# hw.net
KiCad netlist of a schematic drawn in EAGLE
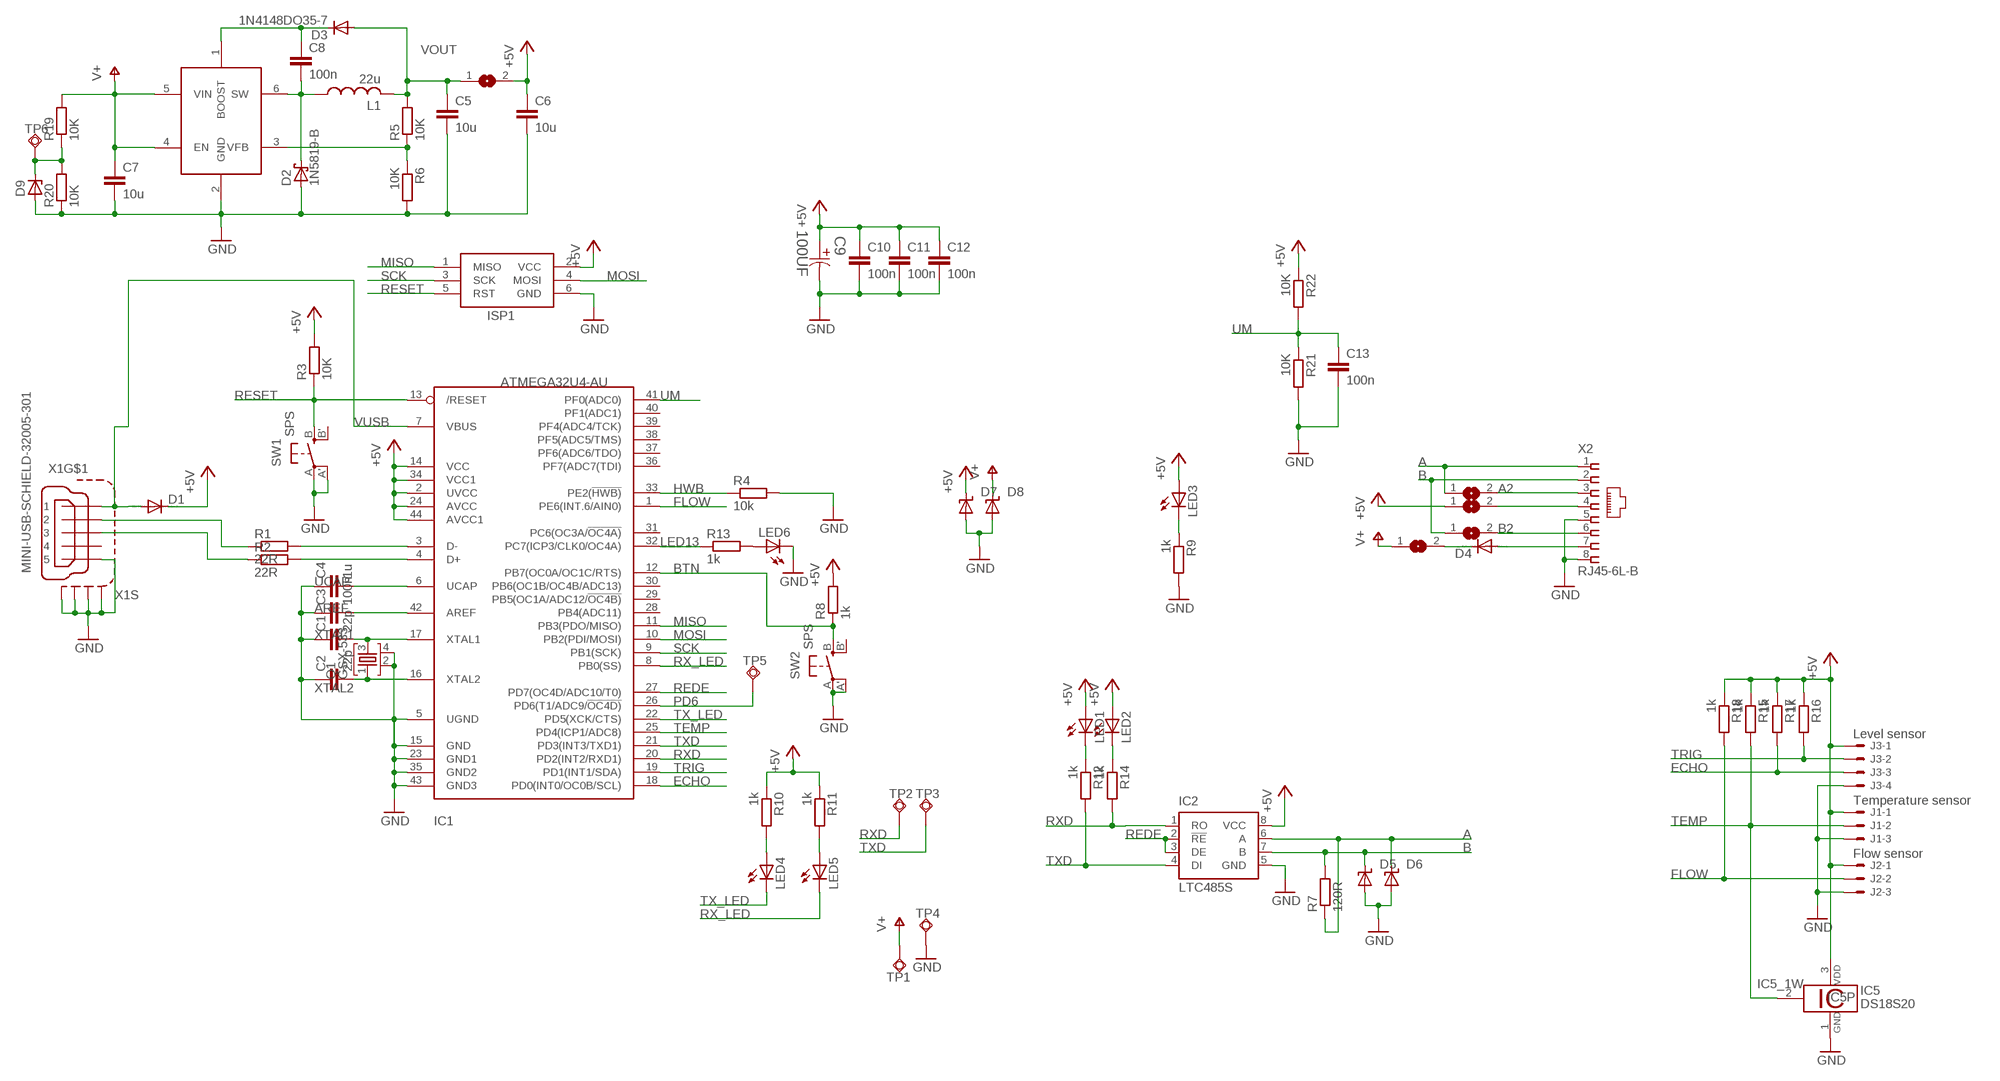
[diagram p0: schematic, sheet 1]

(export (version "E")
  (design (tool "Eeschema 10.0.6"))
  (components
    (comp (ref "C1")
      (value "22p")
      (footprint "eagle-import:C0805K")
      (libsource (lib "eagle-import") (part "C-EUC0805K"))
    )
    (comp (ref "C2")
      (value "22p")
      (footprint "eagle-import:C0805K")
      (libsource (lib "eagle-import") (part "C-EUC0805K"))
    )
    (comp (ref "C3")
      (value "100n")
      (footprint "eagle-import:C0805K")
      (libsource (lib "eagle-import") (part "C-EUC0805K"))
    )
    (comp (ref "C4")
      (value "1u")
      (footprint "eagle-import:C0805K")
      (libsource (lib "eagle-import") (part "C-EUC0805K"))
    )
    (comp (ref "C5")
      (value "10u")
      (footprint "eagle-import:C0805K")
      (libsource (lib "eagle-import") (part "C-EUC0805K"))
    )
    (comp (ref "C6")
      (value "10u")
      (footprint "eagle-import:C0805K")
      (libsource (lib "eagle-import") (part "C-EUC0805K"))
    )
    (comp (ref "C7")
      (value "10u")
      (footprint "eagle-import:C0805K")
      (libsource (lib "eagle-import") (part "C-EUC0805K"))
    )
    (comp (ref "C8")
      (value "100n")
      (footprint "eagle-import:C0805K")
      (libsource (lib "eagle-import") (part "C-EUC0805K"))
    )
    (comp (ref "C9")
      (value "100UF")
      (footprint "eagle-import:CAPAE660X610N")
      (fields (field (name "MPN") "EEE-FK0J101AP") (field (name "TOLERANCE") "±20 %"))
      (libsource (lib "eagle-import") (part "EEE--CASE-DFK0J101AP"))
    )
    (comp (ref "C10")
      (value "100n")
      (footprint "eagle-import:C0805K")
      (libsource (lib "eagle-import") (part "C-EUC0805K"))
    )
    (comp (ref "C11")
      (value "100n")
      (footprint "eagle-import:C0805K")
      (libsource (lib "eagle-import") (part "C-EUC0805K"))
    )
    (comp (ref "C12")
      (value "100n")
      (footprint "eagle-import:C0805K")
      (libsource (lib "eagle-import") (part "C-EUC0805K"))
    )
    (comp (ref "C13")
      (value "100n")
      (footprint "eagle-import:C0805K")
      (libsource (lib "eagle-import") (part "C-EUC0805K"))
    )
    (comp (ref "D1")
      (value "DIODE-MICROMELF-W")
      (footprint "eagle-import:MICROMELF-W")
      (libsource (lib "eagle-import") (part "DIODE-MICROMELF-W"))
    )
    (comp (ref "D2")
      (value "1N5819-B")
      (footprint "eagle-import:DO41-7.6")
      (libsource (lib "eagle-import") (part "1N5819-B"))
    )
    (comp (ref "D3")
      (value "1N4148DO35-7")
      (footprint "eagle-import:DO35-7")
      (libsource (lib "eagle-import") (part "1N4148DO35-7"))
    )
    (comp (ref "D4")
      (value "DIODE-MINIMELF")
      (footprint "eagle-import:MINIMELF")
      (libsource (lib "eagle-import") (part "diode_210_DIODE-MINIMELF"))
    )
    (comp (ref "D5")
      (value "SUPPRESSOR-SMBG")
      (footprint "eagle-import:SMBG")
      (libsource (lib "eagle-import") (part "SUPPRESSOR-SMBG"))
    )
    (comp (ref "D6")
      (value "SUPPRESSOR-SMBG")
      (footprint "eagle-import:SMBG")
      (libsource (lib "eagle-import") (part "SUPPRESSOR-SMBG"))
    )
    (comp (ref "D7")
      (value "SUPPRESSOR-SMBG")
      (footprint "eagle-import:SMBG")
      (libsource (lib "eagle-import") (part "SUPPRESSOR-SMBG"))
    )
    (comp (ref "D8")
      (value "SUPPRESSOR-SMBG")
      (footprint "eagle-import:SMBG")
      (libsource (lib "eagle-import") (part "SUPPRESSOR-SMBG"))
    )
    (comp (ref "D9")
      (value "ZENER-DIODESMB")
      (footprint "eagle-import:SMB")
      (libsource (lib "eagle-import") (part "ZENER-DIODESMB"))
    )
    (comp (ref "IC1")
      (value "ATMEGA32U4-AU")
      (footprint "eagle-import:TQFP44")
      (libsource (lib "eagle-import") (part "ATMEGA32U4-AU"))
    )
    (comp (ref "IC2")
      (value "LTC485S")
      (footprint "eagle-import:SOIC8")
      (libsource (lib "eagle-import") (part "LTC485S"))
    )
    (comp (ref "IC3")
      (value "MCP16301/H")
      (footprint "eagle-import:SOT23-6")
      (libsource (lib "eagle-import") (part "MCP16301/H"))
    )
    (comp (ref "IC5")
      (value "DS18S20")
      (footprint "eagle-import:TO92-")
      (fields (field (name "SPICEPREFIX") "X"))
      (libsource (lib "eagle-import") (part "DS18S20"))
    )
    (comp (ref "ISP1")
      (value "AVRISP-6")
      (footprint "eagle-import:AVRISP")
      (libsource (lib "eagle-import") (part "AVRISP-6"))
    )
    (comp (ref "J1")
      (value "Temperature sensor")
      (footprint "eagle-import:6410-03")
      (fields (field (name "MF") "MOLEX"))
      (libsource (lib "eagle-import") (part "22-?-0327-2031"))
    )
    (comp (ref "J2")
      (value "Flow sensor")
      (footprint "eagle-import:6410-03")
      (fields (field (name "MF") "MOLEX"))
      (libsource (lib "eagle-import") (part "22-?-0327-2031"))
    )
    (comp (ref "J3")
      (value "Level sensor")
      (footprint "eagle-import:6410-04")
      (fields (field (name "MF") "MOLEX"))
      (libsource (lib "eagle-import") (part "22-?-0427-2041"))
    )
    (comp (ref "L1")
      (value "22u")
      (footprint "eagle-import:0207_12")
      (libsource (lib "eagle-import") (part "L-US0207/12"))
    )
    (comp (ref "LED1")
      (value "LEDCHIPLED_0805")
      (footprint "eagle-import:CHIPLED_0805")
      (libsource (lib "eagle-import") (part "LEDCHIPLED_0805"))
    )
    (comp (ref "LED2")
      (value "LEDCHIPLED_0805")
      (footprint "eagle-import:CHIPLED_0805")
      (libsource (lib "eagle-import") (part "LEDCHIPLED_0805"))
    )
    (comp (ref "LED3")
      (value "LEDCHIPLED_0805")
      (footprint "eagle-import:CHIPLED_0805")
      (libsource (lib "eagle-import") (part "LEDCHIPLED_0805"))
    )
    (comp (ref "LED4")
      (value "LEDCHIPLED_0805")
      (footprint "eagle-import:CHIPLED_0805")
      (libsource (lib "eagle-import") (part "LEDCHIPLED_0805"))
    )
    (comp (ref "LED5")
      (value "LEDCHIPLED_0805")
      (footprint "eagle-import:CHIPLED_0805")
      (libsource (lib "eagle-import") (part "LEDCHIPLED_0805"))
    )
    (comp (ref "LED6")
      (value "LEDCHIPLED_0805")
      (footprint "eagle-import:CHIPLED_0805")
      (libsource (lib "eagle-import") (part "LEDCHIPLED_0805"))
    )
    (comp (ref "Q1")
      (value "GSX-533")
      (footprint "eagle-import:5032")
      (libsource (lib "eagle-import") (part "GSX-533"))
    )
    (comp (ref "R1")
      (value "22R")
      (footprint "eagle-import:M0805")
      (libsource (lib "eagle-import") (part "R-EU_M0805"))
    )
    (comp (ref "R2")
      (value "22R")
      (footprint "eagle-import:M0805")
      (libsource (lib "eagle-import") (part "R-EU_M0805"))
    )
    (comp (ref "R3")
      (value "10K")
      (footprint "eagle-import:M0805")
      (libsource (lib "eagle-import") (part "R-EU_M0805"))
    )
    (comp (ref "R4")
      (value "10k")
      (footprint "eagle-import:M0805")
      (libsource (lib "eagle-import") (part "R-EU_M0805"))
    )
    (comp (ref "R5")
      (value "10K")
      (footprint "eagle-import:M0805")
      (libsource (lib "eagle-import") (part "R-EU_M0805"))
    )
    (comp (ref "R6")
      (value "10K")
      (footprint "eagle-import:M0805")
      (libsource (lib "eagle-import") (part "R-EU_M0805"))
    )
    (comp (ref "R7")
      (value "120R")
      (footprint "eagle-import:M0805")
      (libsource (lib "eagle-import") (part "R-EU_M0805"))
    )
    (comp (ref "R8")
      (value "1k")
      (footprint "eagle-import:M0805")
      (libsource (lib "eagle-import") (part "R-EU_M0805"))
    )
    (comp (ref "R9")
      (value "1k")
      (footprint "eagle-import:M0805")
      (libsource (lib "eagle-import") (part "R-EU_M0805"))
    )
    (comp (ref "R10")
      (value "1k")
      (footprint "eagle-import:M0805")
      (libsource (lib "eagle-import") (part "R-EU_M0805"))
    )
    (comp (ref "R11")
      (value "1k")
      (footprint "eagle-import:M0805")
      (libsource (lib "eagle-import") (part "R-EU_M0805"))
    )
    (comp (ref "R12")
      (value "1k")
      (footprint "eagle-import:M0805")
      (libsource (lib "eagle-import") (part "R-EU_M0805"))
    )
    (comp (ref "R13")
      (value "1k")
      (footprint "eagle-import:M0805")
      (libsource (lib "eagle-import") (part "R-EU_M0805"))
    )
    (comp (ref "R14")
      (value "1k")
      (footprint "eagle-import:M0805")
      (libsource (lib "eagle-import") (part "R-EU_M0805"))
    )
    (comp (ref "R15")
      (value "1k")
      (footprint "eagle-import:M0805")
      (libsource (lib "eagle-import") (part "R-EU_M0805"))
    )
    (comp (ref "R16")
      (value "1k")
      (footprint "eagle-import:M0805")
      (libsource (lib "eagle-import") (part "R-EU_M0805"))
    )
    (comp (ref "R17")
      (value "1k")
      (footprint "eagle-import:M0805")
      (libsource (lib "eagle-import") (part "R-EU_M0805"))
    )
    (comp (ref "R18")
      (value "1k")
      (footprint "eagle-import:M0805")
      (libsource (lib "eagle-import") (part "R-EU_M0805"))
    )
    (comp (ref "R19")
      (value "10K")
      (footprint "eagle-import:M0805")
      (libsource (lib "eagle-import") (part "R-EU_M0805"))
    )
    (comp (ref "R20")
      (value "10K")
      (footprint "eagle-import:M0805")
      (libsource (lib "eagle-import") (part "R-EU_M0805"))
    )
    (comp (ref "R21")
      (value "10K")
      (footprint "eagle-import:M0805")
      (libsource (lib "eagle-import") (part "R-EU_M0805"))
    )
    (comp (ref "R22")
      (value "10K")
      (footprint "eagle-import:M0805")
      (libsource (lib "eagle-import") (part "R-EU_M0805"))
    )
    (comp (ref "SJ1") (value "SJ") (footprint "eagle-import:SJ") (libsource (lib "eagle-import") (part "SJ")))
    (comp (ref "SJ2") (value "SJ") (footprint "eagle-import:SJ") (libsource (lib "eagle-import") (part "SJ")))
    (comp (ref "SJ3") (value "SJ") (footprint "eagle-import:SJ") (libsource (lib "eagle-import") (part "SJ")))
    (comp (ref "SJ4") (value "SJ") (footprint "eagle-import:SJ") (libsource (lib "eagle-import") (part "SJ")))
    (comp (ref "SJ5") (value "SJ") (footprint "eagle-import:SJ") (libsource (lib "eagle-import") (part "SJ")))
    (comp (ref "SW1")
      (value "SPS")
      (footprint "eagle-import:EVQ-Q2")
      (libsource (lib "eagle-import") (part "SPST_TACT-EVQQ2"))
    )
    (comp (ref "SW2")
      (value "SPS")
      (footprint "eagle-import:EVQ-Q2")
      (libsource (lib "eagle-import") (part "SPST_TACT-EVQQ2"))
    )
    (comp (ref "TP1")
      (value "TPSQTP20SQ")
      (footprint "eagle-import:TP20SQ")
      (libsource (lib "eagle-import") (part "TPSQTP20SQ"))
    )
    (comp (ref "TP2")
      (value "TPSQTP20SQ")
      (footprint "eagle-import:TP20SQ")
      (libsource (lib "eagle-import") (part "TPSQTP20SQ"))
    )
    (comp (ref "TP3")
      (value "TPSQTP20SQ")
      (footprint "eagle-import:TP20SQ")
      (libsource (lib "eagle-import") (part "TPSQTP20SQ"))
    )
    (comp (ref "TP4")
      (value "TPSQTP20SQ")
      (footprint "eagle-import:TP20SQ")
      (libsource (lib "eagle-import") (part "TPSQTP20SQ"))
    )
    (comp (ref "TP5")
      (value "TPSQTP20SQ")
      (footprint "eagle-import:TP20SQ")
      (libsource (lib "eagle-import") (part "TPSQTP20SQ"))
    )
    (comp (ref "TP6")
      (value "TPSQTP20SQ")
      (footprint "eagle-import:TP20SQ")
      (libsource (lib "eagle-import") (part "TPSQTP20SQ"))
    )
    (comp (ref "X1")
      (value "MINI-USB-SCHIELD-32005-301")
      (footprint "eagle-import:32005-301")
      (libsource (lib "eagle-import") (part "MINI-USB-SCHIELD-32005-301"))
    )
    (comp (ref "X2")
      (value "RJ45-6L-B")
      (footprint "eagle-import:RJ45-NO-SHIELD")
      (libsource (lib "eagle-import") (part "RJ45-6L-B"))
    )
  )
  (nets
    (net (code "1") (name "+5V") (class "Default")
      (node (ref "C10") (pin "1") (pinfunction "1_1") (pintype "passive"))
      (node (ref "C11") (pin "1") (pinfunction "1_1") (pintype "passive"))
      (node (ref "C12") (pin "1") (pinfunction "1_1") (pintype "passive"))
      (node (ref "C6") (pin "1") (pinfunction "1_1") (pintype "passive"))
      (node (ref "C9") (pin "1") (pinfunction "1_1") (pintype "passive"))
      (node (ref "D1") (pin "C") (pinfunction "C_C") (pintype "passive"))
      (node (ref "D7") (pin "C") (pinfunction "C_C") (pintype "passive"))
      (node (ref "IC1") (pin "14") (pinfunction "VCC_14") (pintype "bidirectional"))
      (node (ref "IC1") (pin "2") (pinfunction "UVCC_2") (pintype "bidirectional"))
      (node (ref "IC1") (pin "24") (pinfunction "AVCC_24") (pintype "bidirectional"))
      (node (ref "IC1") (pin "34") (pinfunction "VCC1_34") (pintype "bidirectional"))
      (node (ref "IC1") (pin "44") (pinfunction "AVCC1_44") (pintype "bidirectional"))
      (node (ref "IC2") (pin "8") (pinfunction "VCC_8") (pintype "input"))
      (node (ref "IC5") (pin "3") (pinfunction "VDD_3") (pintype "power_in"))
      (node (ref "ISP1") (pin "2") (pinfunction "VCC_2") (pintype "power_in"))
      (node (ref "J1") (pin "1") (pinfunction "S_1") (pintype "passive"))
      (node (ref "J2") (pin "1") (pinfunction "S_1") (pintype "passive"))
      (node (ref "J3") (pin "1") (pinfunction "S_1") (pintype "passive"))
      (node (ref "LED1") (pin "A") (pinfunction "A_A") (pintype "passive"))
      (node (ref "LED2") (pin "A") (pinfunction "A_A") (pintype "passive"))
      (node (ref "LED3") (pin "A") (pinfunction "A_A") (pintype "passive"))
      (node (ref "R10") (pin "1") (pinfunction "1_1") (pintype "passive"))
      (node (ref "R11") (pin "1") (pinfunction "1_1") (pintype "passive"))
      (node (ref "R15") (pin "1") (pinfunction "1_1") (pintype "passive"))
      (node (ref "R16") (pin "1") (pinfunction "1_1") (pintype "passive"))
      (node (ref "R17") (pin "1") (pinfunction "1_1") (pintype "passive"))
      (node (ref "R18") (pin "1") (pinfunction "1_1") (pintype "passive"))
      (node (ref "R22") (pin "1") (pinfunction "1_1") (pintype "passive"))
      (node (ref "R3") (pin "2") (pinfunction "2_2") (pintype "passive"))
      (node (ref "R8") (pin "2") (pinfunction "2_2") (pintype "passive"))
      (node (ref "SJ4") (pin "1") (pinfunction "1_1") (pintype "passive"))
      (node (ref "SJ5") (pin "2") (pinfunction "2_2") (pintype "passive"))
    )
    (net (code "2") (name "/A") (class "Default")
      (node (ref "D6") (pin "C") (pinfunction "C_C") (pintype "passive"))
      (node (ref "IC2") (pin "6") (pinfunction "A_6") (pintype "bidirectional"))
      (node (ref "R7") (pin "1") (pinfunction "1_1") (pintype "passive"))
      (node (ref "SJ1") (pin "1") (pinfunction "1_1") (pintype "passive"))
      (node (ref "X2") (pin "1") (pinfunction "1_1") (pintype "passive"))
    )
    (net (code "3") (name "/A2") (class "Default")
      (node (ref "SJ1") (pin "2") (pinfunction "2_2") (pintype "passive"))
      (node (ref "X2") (pin "3") (pinfunction "3_3") (pintype "passive"))
    )
    (net (code "4") (name "/AREF") (class "Default")
      (node (ref "C3") (pin "2") (pinfunction "2_2") (pintype "passive"))
      (node (ref "IC1") (pin "42") (pinfunction "AREF_42") (pintype "bidirectional"))
    )
    (net (code "5") (name "/B") (class "Default")
      (node (ref "D5") (pin "C") (pinfunction "C_C") (pintype "passive"))
      (node (ref "IC2") (pin "7") (pinfunction "B_7") (pintype "bidirectional"))
      (node (ref "R7") (pin "2") (pinfunction "2_2") (pintype "passive"))
      (node (ref "SJ2") (pin "1") (pinfunction "1_1") (pintype "passive"))
      (node (ref "X2") (pin "2") (pinfunction "2_2") (pintype "passive"))
    )
    (net (code "6") (name "/B2") (class "Default")
      (node (ref "SJ2") (pin "2") (pinfunction "2_2") (pintype "passive"))
      (node (ref "X2") (pin "6") (pinfunction "6_6") (pintype "passive"))
    )
    (net (code "7") (name "/BTN") (class "Default")
      (node (ref "IC1") (pin "12") (pinfunction "PB7(OC0A/OC1C/RTS)_12") (pintype "bidirectional"))
      (node (ref "R8") (pin "1") (pinfunction "1_1") (pintype "passive"))
      (node (ref "SW2") (pin "B") (pinfunction "S_B") (pintype "passive"))
    )
    (net (code "8") (name "/ECHO") (class "Default")
      (node (ref "IC1") (pin "18") (pinfunction "PD0(INT0/OC0B/SCL)_18") (pintype "bidirectional"))
      (node (ref "J3") (pin "3") (pinfunction "S_3") (pintype "passive"))
      (node (ref "R17") (pin "2") (pinfunction "2_2") (pintype "passive"))
    )
    (net (code "9") (name "/FLOW") (class "Default")
      (node (ref "IC1") (pin "1") (pinfunction "PE6(INT.6/AIN0)_1") (pintype "bidirectional"))
      (node (ref "J2") (pin "2") (pinfunction "S_2") (pintype "passive"))
      (node (ref "R18") (pin "2") (pinfunction "2_2") (pintype "passive"))
    )
    (net (code "10") (name "/HWB") (class "Default")
      (node (ref "IC1") (pin "33") (pinfunction "PE2(~{HWB})_33") (pintype "bidirectional"))
      (node (ref "R4") (pin "1") (pinfunction "1_1") (pintype "passive"))
    )
    (net (code "11") (name "/LED13") (class "Default")
      (node (ref "IC1") (pin "32") (pinfunction "PC7(ICP3/CLK0/OC4A)_32") (pintype "bidirectional"))
      (node (ref "R13") (pin "1") (pinfunction "1_1") (pintype "passive"))
    )
    (net (code "12") (name "/MISO") (class "Default")
      (node (ref "IC1") (pin "11") (pinfunction "PB3(PDO/MISO)_11") (pintype "bidirectional"))
      (node (ref "ISP1") (pin "1") (pinfunction "MISO_1") (pintype "input"))
    )
    (net (code "13") (name "/MOSI") (class "Default")
      (node (ref "IC1") (pin "10") (pinfunction "PB2(PDI/MOSI)_10") (pintype "bidirectional"))
      (node (ref "ISP1") (pin "4") (pinfunction "MOSI_4") (pintype "output"))
    )
    (net (code "14") (name "/PD6") (class "Default")
      (node (ref "IC1") (pin "26") (pinfunction "PD6(T1/ADC9/~{OC4D})_26") (pintype "bidirectional"))
      (node (ref "TP5") (pin "TP") (pinfunction "TP_TP") (pintype "input"))
    )
    (net (code "15") (name "/REDE") (class "Default")
      (node (ref "IC1") (pin "27") (pinfunction "PD7(OC4D/ADC10/T0)_27") (pintype "bidirectional"))
      (node (ref "IC2") (pin "2") (pinfunction "~{RE}_2") (pintype "input"))
      (node (ref "IC2") (pin "3") (pinfunction "DE_3") (pintype "input"))
    )
    (net (code "16") (name "/RESET") (class "Default")
      (node (ref "IC1") (pin "13") (pinfunction "/RESET_13") (pintype "bidirectional"))
      (node (ref "ISP1") (pin "5") (pinfunction "RST_5") (pintype "output"))
      (node (ref "R3") (pin "1") (pinfunction "1_1") (pintype "passive"))
      (node (ref "SW1") (pin "B") (pinfunction "S_B") (pintype "passive"))
    )
    (net (code "17") (name "/RXD") (class "Default")
      (node (ref "IC1") (pin "20") (pinfunction "PD2(INT2/RXD1)_20") (pintype "bidirectional"))
      (node (ref "IC2") (pin "1") (pinfunction "RO_1") (pintype "output"))
      (node (ref "R14") (pin "2") (pinfunction "2_2") (pintype "passive"))
      (node (ref "TP2") (pin "TP") (pinfunction "TP_TP") (pintype "input"))
    )
    (net (code "18") (name "/RX_LED") (class "Default")
      (node (ref "IC1") (pin "8") (pinfunction "PB0(SS)_8") (pintype "bidirectional"))
      (node (ref "LED5") (pin "C") (pinfunction "C_C") (pintype "passive"))
    )
    (net (code "19") (name "/SCK") (class "Default")
      (node (ref "IC1") (pin "9") (pinfunction "PB1(SCK)_9") (pintype "bidirectional"))
      (node (ref "ISP1") (pin "3") (pinfunction "SCK_3") (pintype "output"))
    )
    (net (code "20") (name "/TEMP") (class "Default")
      (node (ref "IC1") (pin "25") (pinfunction "PD4(ICP1/ADC8)_25") (pintype "bidirectional"))
      (node (ref "IC5") (pin "2") (pinfunction "1W_2") (pintype "power_in"))
      (node (ref "J1") (pin "2") (pinfunction "S_2") (pintype "passive"))
      (node (ref "R15") (pin "2") (pinfunction "2_2") (pintype "passive"))
    )
    (net (code "21") (name "/TRIG") (class "Default")
      (node (ref "IC1") (pin "19") (pinfunction "PD1(INT1/SDA)_19") (pintype "bidirectional"))
      (node (ref "J3") (pin "2") (pinfunction "S_2") (pintype "passive"))
      (node (ref "R16") (pin "2") (pinfunction "2_2") (pintype "passive"))
    )
    (net (code "22") (name "/TXD") (class "Default")
      (node (ref "IC1") (pin "21") (pinfunction "PD3(INT3/TXD1)_21") (pintype "bidirectional"))
      (node (ref "IC2") (pin "4") (pinfunction "DI_4") (pintype "input"))
      (node (ref "R12") (pin "2") (pinfunction "2_2") (pintype "passive"))
      (node (ref "TP3") (pin "TP") (pinfunction "TP_TP") (pintype "input"))
    )
    (net (code "23") (name "/TX_LED") (class "Default")
      (node (ref "IC1") (pin "22") (pinfunction "PD5(XCK/CTS)_22") (pintype "bidirectional"))
      (node (ref "LED4") (pin "C") (pinfunction "C_C") (pintype "passive"))
    )
    (net (code "24") (name "/UCAP") (class "Default")
      (node (ref "C4") (pin "2") (pinfunction "2_2") (pintype "passive"))
      (node (ref "IC1") (pin "6") (pinfunction "UCAP_6") (pintype "bidirectional"))
    )
    (net (code "25") (name "/UM") (class "Default")
      (node (ref "C13") (pin "1") (pinfunction "1_1") (pintype "passive"))
      (node (ref "IC1") (pin "41") (pinfunction "PF0(ADC0)_41") (pintype "bidirectional"))
      (node (ref "R21") (pin "1") (pinfunction "1_1") (pintype "passive"))
      (node (ref "R22") (pin "2") (pinfunction "2_2") (pintype "passive"))
    )
    (net (code "26") (name "/VOUT") (class "Default")
      (node (ref "C5") (pin "1") (pinfunction "1_1") (pintype "passive"))
      (node (ref "D3") (pin "A") (pinfunction "A_A") (pintype "passive"))
      (node (ref "L1") (pin "2") (pinfunction "2_2") (pintype "passive"))
      (node (ref "R5") (pin "2") (pinfunction "2_2") (pintype "passive"))
      (node (ref "SJ5") (pin "1") (pinfunction "1_1") (pintype "passive"))
    )
    (net (code "27") (name "/VUSB") (class "Default")
      (node (ref "D1") (pin "A") (pinfunction "A_A") (pintype "passive"))
      (node (ref "IC1") (pin "7") (pinfunction "VBUS_7") (pintype "bidirectional"))
      (node (ref "X1") (pin "1") (pinfunction "1_1") (pintype "passive"))
    )
    (net (code "28") (name "/XTAL1") (class "Default")
      (node (ref "C1") (pin "2") (pinfunction "2_2") (pintype "passive"))
      (node (ref "IC1") (pin "17") (pinfunction "XTAL1_17") (pintype "bidirectional"))
      (node (ref "Q1") (pin "3") (pinfunction "XTAL2_3") (pintype "passive"))
    )
    (net (code "29") (name "/XTAL2") (class "Default")
      (node (ref "C2") (pin "2") (pinfunction "2_2") (pintype "passive"))
      (node (ref "IC1") (pin "16") (pinfunction "XTAL2_16") (pintype "bidirectional"))
      (node (ref "Q1") (pin "1") (pinfunction "XTAL1_1") (pintype "passive"))
    )
    (net (code "30") (name "GND") (class "Default")
      (node (ref "C1") (pin "1") (pinfunction "1_1") (pintype "passive"))
      (node (ref "C10") (pin "2") (pinfunction "2_2") (pintype "passive"))
      (node (ref "C11") (pin "2") (pinfunction "2_2") (pintype "passive"))
      (node (ref "C12") (pin "2") (pinfunction "2_2") (pintype "passive"))
      (node (ref "C13") (pin "2") (pinfunction "2_2") (pintype "passive"))
      (node (ref "C2") (pin "1") (pinfunction "1_1") (pintype "passive"))
      (node (ref "C3") (pin "1") (pinfunction "1_1") (pintype "passive"))
      (node (ref "C4") (pin "1") (pinfunction "1_1") (pintype "passive"))
      (node (ref "C5") (pin "2") (pinfunction "2_2") (pintype "passive"))
      (node (ref "C6") (pin "2") (pinfunction "2_2") (pintype "passive"))
      (node (ref "C7") (pin "2") (pinfunction "2_2") (pintype "passive"))
      (node (ref "C9") (pin "2") (pinfunction "2_2") (pintype "passive"))
      (node (ref "D2") (pin "A") (pinfunction "A_A") (pintype "passive"))
      (node (ref "D5") (pin "A") (pinfunction "A_A") (pintype "passive"))
      (node (ref "D6") (pin "A") (pinfunction "A_A") (pintype "passive"))
      (node (ref "D7") (pin "A") (pinfunction "A_A") (pintype "passive"))
      (node (ref "D8") (pin "A") (pinfunction "A_A") (pintype "passive"))
      (node (ref "D9") (pin "A") (pinfunction "A_A") (pintype "passive"))
      (node (ref "IC1") (pin "15") (pinfunction "GND_15") (pintype "bidirectional"))
      (node (ref "IC1") (pin "23") (pinfunction "GND1_23") (pintype "bidirectional"))
      (node (ref "IC1") (pin "35") (pinfunction "GND2_35") (pintype "bidirectional"))
      (node (ref "IC1") (pin "43") (pinfunction "GND3_43") (pintype "bidirectional"))
      (node (ref "IC1") (pin "5") (pinfunction "UGND_5") (pintype "bidirectional"))
      (node (ref "IC2") (pin "5") (pinfunction "GND_5") (pintype "input"))
      (node (ref "IC3") (pin "2") (pinfunction "GND_2") (pintype "power_in"))
      (node (ref "IC5") (pin "1") (pinfunction "GND_1") (pintype "power_in"))
      (node (ref "ISP1") (pin "6") (pinfunction "GND_6") (pintype "power_in"))
      (node (ref "J1") (pin "3") (pinfunction "S_3") (pintype "passive"))
      (node (ref "J2") (pin "3") (pinfunction "S_3") (pintype "passive"))
      (node (ref "J3") (pin "4") (pinfunction "S_4") (pintype "passive"))
      (node (ref "LED6") (pin "C") (pinfunction "C_C") (pintype "passive"))
      (node (ref "Q1") (pin "2") (pinfunction "GND1_2") (pintype "passive"))
      (node (ref "Q1") (pin "4") (pinfunction "GND2_4") (pintype "passive"))
      (node (ref "R20") (pin "1") (pinfunction "1_1") (pintype "passive"))
      (node (ref "R21") (pin "2") (pinfunction "2_2") (pintype "passive"))
      (node (ref "R4") (pin "2") (pinfunction "2_2") (pintype "passive"))
      (node (ref "R6") (pin "2") (pinfunction "2_2") (pintype "passive"))
      (node (ref "R9") (pin "2") (pinfunction "2_2") (pintype "passive"))
      (node (ref "SW1") (pin "A") (pinfunction "P_A") (pintype "passive"))
      (node (ref "SW1") (pin "A'") (pinfunction "P1_A'") (pintype "passive"))
      (node (ref "SW2") (pin "A") (pinfunction "P_A") (pintype "passive"))
      (node (ref "SW2") (pin "A'") (pinfunction "P1_A'") (pintype "passive"))
      (node (ref "TP4") (pin "TP") (pinfunction "TP_TP") (pintype "input"))
      (node (ref "X1") (pin "5") (pinfunction "5_5") (pintype "passive"))
      (node (ref "X1") (pin "M1") (pinfunction "S1_M1") (pintype "passive"))
      (node (ref "X1") (pin "M2") (pinfunction "S2_M2") (pintype "passive"))
      (node (ref "X1") (pin "M3") (pinfunction "S3_M3") (pintype "passive"))
      (node (ref "X1") (pin "M4") (pinfunction "S4_M4") (pintype "passive"))
      (node (ref "X2") (pin "5") (pinfunction "5_5") (pintype "passive"))
      (node (ref "X2") (pin "8") (pinfunction "8_8") (pintype "passive"))
    )
    (net (code "31") (name "Net-(D4-PadA)") (class "Default")
      (node (ref "D4") (pin "A") (pinfunction "A_A") (pintype "passive"))
      (node (ref "X2") (pin "7") (pinfunction "7_7") (pintype "passive"))
    )
    (net (code "32") (name "Net-(D4-PadC)") (class "Default")
      (node (ref "D4") (pin "C") (pinfunction "C_C") (pintype "passive"))
      (node (ref "SJ3") (pin "2") (pinfunction "2_2") (pintype "passive"))
    )
    (net (code "33") (name "Net-(D9-PadC)") (class "Default")
      (node (ref "D9") (pin "C") (pinfunction "C_C") (pintype "passive"))
      (node (ref "R19") (pin "1") (pinfunction "1_1") (pintype "passive"))
      (node (ref "R20") (pin "2") (pinfunction "2_2") (pintype "passive"))
      (node (ref "TP6") (pin "TP") (pinfunction "TP_TP") (pintype "input"))
    )
    (net (code "34") (name "Net-(IC1-D+)") (class "Default")
      (node (ref "IC1") (pin "4") (pinfunction "D+_4") (pintype "bidirectional"))
      (node (ref "R2") (pin "2") (pinfunction "2_2") (pintype "passive"))
    )
    (net (code "35") (name "Net-(IC1-D-)") (class "Default")
      (node (ref "IC1") (pin "3") (pinfunction "D-_3") (pintype "bidirectional"))
      (node (ref "R1") (pin "2") (pinfunction "2_2") (pintype "passive"))
    )
    (net (code "36") (name "Net-(IC3-BOOST)") (class "Default")
      (node (ref "C8") (pin "1") (pinfunction "1_1") (pintype "passive"))
      (node (ref "D3") (pin "C") (pinfunction "C_C") (pintype "passive"))
      (node (ref "IC3") (pin "1") (pinfunction "BOOST_1") (pintype "bidirectional"))
    )
    (net (code "37") (name "Net-(IC3-SW)") (class "Default")
      (node (ref "C8") (pin "2") (pinfunction "2_2") (pintype "passive"))
      (node (ref "D2") (pin "C") (pinfunction "C_C") (pintype "passive"))
      (node (ref "IC3") (pin "6") (pinfunction "SW_6") (pintype "power_in"))
      (node (ref "L1") (pin "1") (pinfunction "1_1") (pintype "passive"))
    )
    (net (code "38") (name "Net-(IC3-VFB)") (class "Default")
      (node (ref "IC3") (pin "3") (pinfunction "VFB_3") (pintype "bidirectional"))
      (node (ref "R5") (pin "1") (pinfunction "1_1") (pintype "passive"))
      (node (ref "R6") (pin "1") (pinfunction "1_1") (pintype "passive"))
    )
    (net (code "39") (name "Net-(LED1-PadC)") (class "Default")
      (node (ref "LED1") (pin "C") (pinfunction "C_C") (pintype "passive"))
      (node (ref "R12") (pin "1") (pinfunction "1_1") (pintype "passive"))
    )
    (net (code "40") (name "Net-(LED2-PadC)") (class "Default")
      (node (ref "LED2") (pin "C") (pinfunction "C_C") (pintype "passive"))
      (node (ref "R14") (pin "1") (pinfunction "1_1") (pintype "passive"))
    )
    (net (code "41") (name "Net-(LED3-PadC)") (class "Default")
      (node (ref "LED3") (pin "C") (pinfunction "C_C") (pintype "passive"))
      (node (ref "R9") (pin "1") (pinfunction "1_1") (pintype "passive"))
    )
    (net (code "42") (name "Net-(LED4-PadA)") (class "Default")
      (node (ref "LED4") (pin "A") (pinfunction "A_A") (pintype "passive"))
      (node (ref "R10") (pin "2") (pinfunction "2_2") (pintype "passive"))
    )
    (net (code "43") (name "Net-(LED5-PadA)") (class "Default")
      (node (ref "LED5") (pin "A") (pinfunction "A_A") (pintype "passive"))
      (node (ref "R11") (pin "2") (pinfunction "2_2") (pintype "passive"))
    )
    (net (code "44") (name "Net-(LED6-PadA)") (class "Default")
      (node (ref "LED6") (pin "A") (pinfunction "A_A") (pintype "passive"))
      (node (ref "R13") (pin "2") (pinfunction "2_2") (pintype "passive"))
    )
    (net (code "45") (name "Net-(R1-Pad1)") (class "Default")
      (node (ref "R1") (pin "1") (pinfunction "1_1") (pintype "passive"))
      (node (ref "X1") (pin "2") (pinfunction "2_2") (pintype "passive"))
    )
    (net (code "46") (name "Net-(R2-Pad1)") (class "Default")
      (node (ref "R2") (pin "1") (pinfunction "1_1") (pintype "passive"))
      (node (ref "X1") (pin "3") (pinfunction "3_3") (pintype "passive"))
    )
    (net (code "47") (name "Net-(SJ4-Pad2)") (class "Default")
      (node (ref "SJ4") (pin "2") (pinfunction "2_2") (pintype "passive"))
      (node (ref "X2") (pin "4") (pinfunction "4_4") (pintype "passive"))
    )
    (net (code "48") (name "V+") (class "Default")
      (node (ref "C7") (pin "1") (pinfunction "1_1") (pintype "passive"))
      (node (ref "D8") (pin "C") (pinfunction "C_C") (pintype "passive"))
      (node (ref "IC3") (pin "4") (pinfunction "EN_4") (pintype "bidirectional"))
      (node (ref "IC3") (pin "5") (pinfunction "VIN_5") (pintype "power_in"))
      (node (ref "R19") (pin "2") (pinfunction "2_2") (pintype "passive"))
      (node (ref "SJ3") (pin "1") (pinfunction "1_1") (pintype "passive"))
      (node (ref "TP1") (pin "TP") (pinfunction "TP_TP") (pintype "input"))
    )
    (net (code "49") (name "unconnected-(IC1-PB4(ADC11)-Pad28)") (class "Default")
      (node (ref "IC1") (pin "28") (pinfunction "PB4(ADC11)_28") (pintype "bidirectional"))
    )
    (net (code "50") (name "unconnected-(IC1-PB5(OC1A{slash}ADC12{slash}~{OC4B})-Pad29)") (class "Default")
      (node (ref "IC1") (pin "29") (pinfunction "PB5(OC1A/ADC12/~{OC4B})_29") (pintype "bidirectional"))
    )
    (net (code "51") (name "unconnected-(IC1-PB6(OC1B{slash}OC4B{slash}ADC13)-Pad30)") (class "Default")
      (node (ref "IC1") (pin "30") (pinfunction "PB6(OC1B/OC4B/ADC13)_30") (pintype "bidirectional"))
    )
    (net (code "52") (name "unconnected-(IC1-PC6(OC3A{slash}~{OC4A})-Pad31)") (class "Default")
      (node (ref "IC1") (pin "31") (pinfunction "PC6(OC3A/~{OC4A})_31") (pintype "bidirectional"))
    )
    (net (code "53") (name "unconnected-(IC1-PF1(ADC1)-Pad40)") (class "Default")
      (node (ref "IC1") (pin "40") (pinfunction "PF1(ADC1)_40") (pintype "bidirectional"))
    )
    (net (code "54") (name "unconnected-(IC1-PF4(ADC4{slash}TCK)-Pad39)") (class "Default")
      (node (ref "IC1") (pin "39") (pinfunction "PF4(ADC4/TCK)_39") (pintype "bidirectional"))
    )
    (net (code "55") (name "unconnected-(IC1-PF5(ADC5{slash}TMS)-Pad38)") (class "Default")
      (node (ref "IC1") (pin "38") (pinfunction "PF5(ADC5/TMS)_38") (pintype "bidirectional"))
    )
    (net (code "56") (name "unconnected-(IC1-PF6(ADC6{slash}TDO)-Pad37)") (class "Default")
      (node (ref "IC1") (pin "37") (pinfunction "PF6(ADC6/TDO)_37") (pintype "bidirectional"))
    )
    (net (code "57") (name "unconnected-(IC1-PF7(ADC7(TDI)-Pad36)") (class "Default")
      (node (ref "IC1") (pin "36") (pinfunction "PF7(ADC7(TDI)_36") (pintype "bidirectional"))
    )
    (net (code "58") (name "unconnected-(SW1-S1-PadB')") (class "Default")
      (node (ref "SW1") (pin "B'") (pinfunction "S1_B'") (pintype "passive"))
    )
    (net (code "59") (name "unconnected-(SW2-S1-PadB')") (class "Default")
      (node (ref "SW2") (pin "B'") (pinfunction "S1_B'") (pintype "passive"))
    )
    (net (code "60") (name "unconnected-(X1-Pad4)") (class "Default")
      (node (ref "X1") (pin "4") (pinfunction "4_4") (pintype "passive"))
    )
  )
)
